# Sheet1.net
KiCad netlist of a schematic drawn in Altium Designer
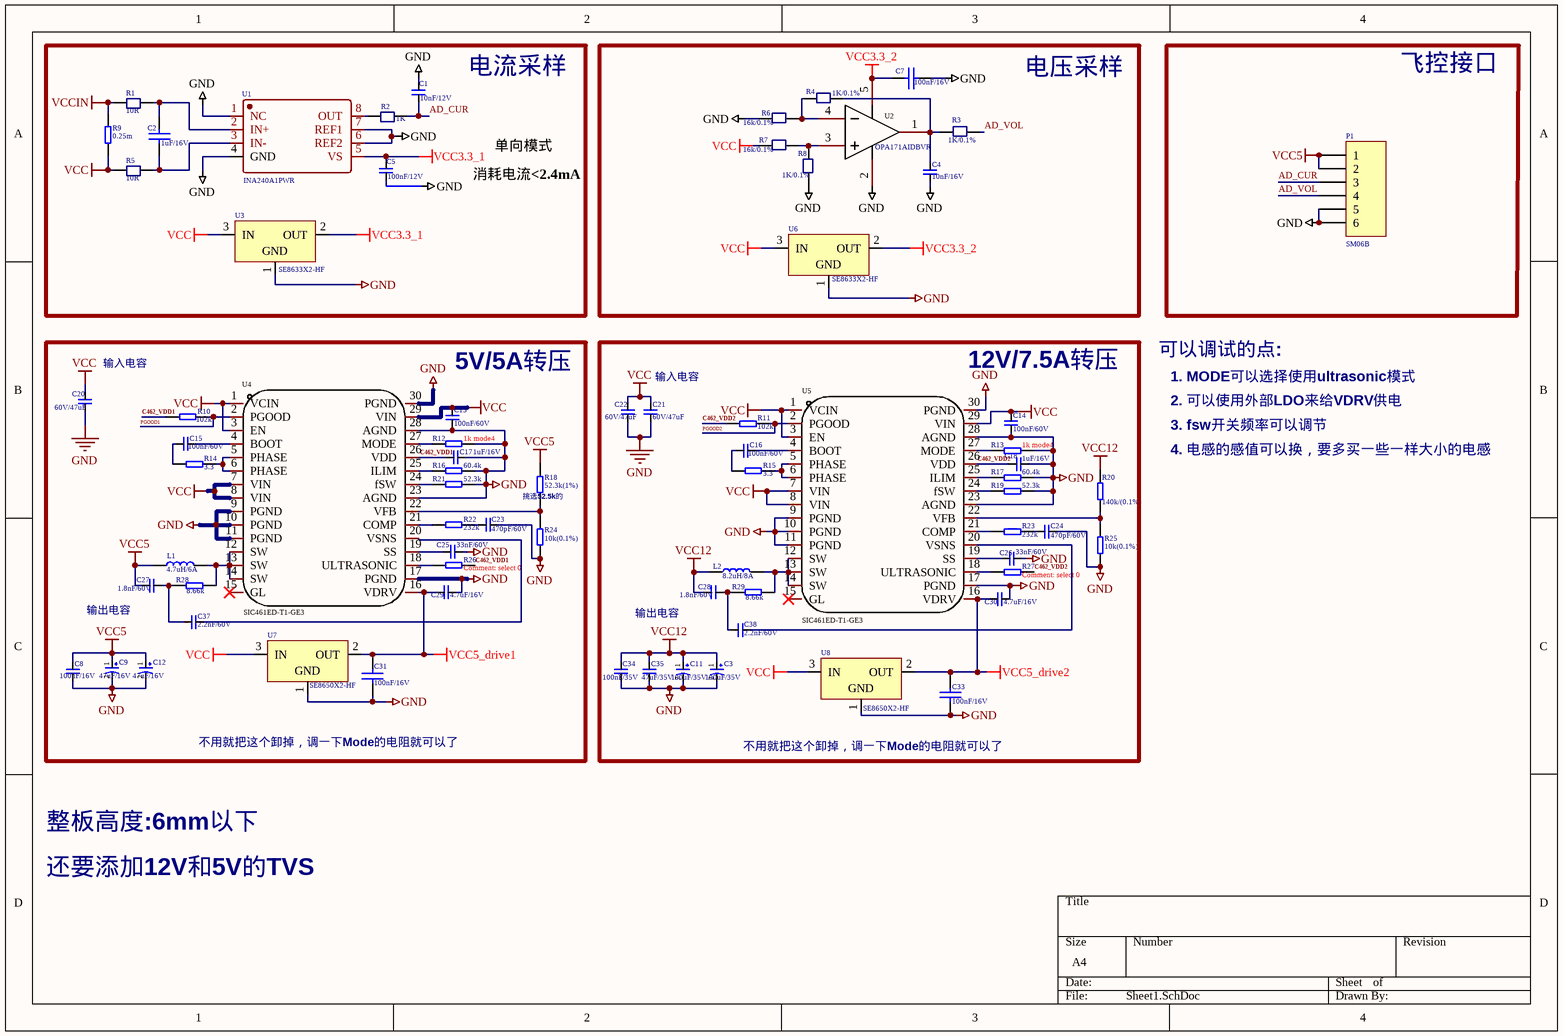
[diagram p0: Sheet1.SchDoc]

(export (version "E")
  (design (tool "Eeschema 10.0.6"))
  (components
    (comp (ref "C1") (value "10nF/12V") (footprint "C0402") (libsource (lib "Schlib1") (part "C")))
    (comp (ref "C2")
      (value "1uF/16V")
      (footprint "C 0603_M")
      (description "Capacitor")
      (fields (field (name "PUBLISHER") "Altium Limited"))
      (libsource (lib "超级电容") (part "Cap"))
    )
    (comp (ref "C3")
      (value "100uF/35V")
      (footprint "CASE-B-3528")
      (description "极性电容\r\n多为大容量铝电解\r\nNPXD0601V101MF\r\n100uF/35V\r\nC2976304")
      (libsource (lib "Schlib1") (part "CP"))
    )
    (comp (ref "C4") (value "10nF/16V") (footprint "C0402") (libsource (lib "Schlib1") (part "C")))
    (comp (ref "C5") (value "100nF/12V") (footprint "C0402") (libsource (lib "Schlib1") (part "C")))
    (comp (ref "C7")
      (value "100nF/16V")
      (footprint "C0402")
      (description "Capacitor")
      (fields (field (name "PUBLISHER") "Altium Limited"))
      (libsource (lib "超级电容") (part "Cap"))
    )
    (comp (ref "C8") (value "100nF/16V") (footprint "C0402") (libsource (lib "Schlib1") (part "C")))
    (comp (ref "C9")
      (value "47uF/16V")
      (footprint "CASE-B-3528")
      (description "极性电容\r\n多为大容量铝电解")
      (libsource (lib "Schlib1") (part "CP"))
    )
    (comp (ref "C11")
      (value "100uF/35V")
      (footprint "CASE-B-3528")
      (description "极性电容\r\n多为大容量铝电解\r\nNPXD0601V101MF\r\n100uF/35V\r\nC2976304")
      (libsource (lib "Schlib1") (part "CP"))
    )
    (comp (ref "C12")
      (value "47uF/16V")
      (footprint "CASE-B-3528")
      (description "极性电容\r\n多为大容量铝电解")
      (libsource (lib "Schlib1") (part "CP"))
    )
    (comp (ref "C13") (value "100nF/60V") (footprint "C0402") (libsource (lib "Schlib1") (part "C")))
    (comp (ref "C14") (value "100nF/60V") (footprint "C0402") (libsource (lib "Schlib1") (part "C")))
    (comp (ref "C15") (value "100nF/60V") (footprint "C0402") (libsource (lib "Schlib1") (part "C")))
    (comp (ref "C16") (value "100nF/60V") (footprint "C0402") (libsource (lib "Schlib1") (part "C")))
    (comp (ref "C17") (value "1uF/16V") (footprint "C0402") (libsource (lib "Schlib1") (part "C")))
    (comp (ref "C18") (value "1uF/16V") (footprint "C0402") (libsource (lib "Schlib1") (part "C")))
    (comp (ref "C20") (value "60V/47uF") (footprint "C 1210") (libsource (lib "Schlib1") (part "C")))
    (comp (ref "C21") (value "60V/47uF") (footprint "C 1210") (libsource (lib "Schlib1") (part "C")))
    (comp (ref "C22") (value "60V/47uF") (footprint "C 1210") (libsource (lib "Schlib1") (part "C")))
    (comp (ref "C23") (value "470pF/60V") (footprint "C0402") (libsource (lib "Schlib1") (part "C")))
    (comp (ref "C24") (value "470pF/60V") (footprint "C 0603_M") (libsource (lib "Schlib1") (part "C")))
    (comp (ref "C25") (value "33nF/60V") (footprint "C0402") (libsource (lib "Schlib1") (part "C")))
    (comp (ref "C26") (value "33nF/60V") (footprint "C0402") (libsource (lib "Schlib1") (part "C")))
    (comp (ref "C27")
      (value "1.8nF/60V")
      (footprint "C0402")
      (description "C1853237")
      (libsource (lib "Schlib1") (part "C"))
    )
    (comp (ref "C28")
      (value "1.8nF/60V")
      (footprint "C0402")
      (description "C1853237")
      (libsource (lib "Schlib1") (part "C"))
    )
    (comp (ref "C29") (value "4.7uF/16V") (footprint "C 0603_M") (libsource (lib "Schlib1") (part "C")))
    (comp (ref "C30") (value "4.7uF/16V") (footprint "C 0603_M") (libsource (lib "Schlib1") (part "C")))
    (comp (ref "C31")
      (value "100nF/16V")
      (footprint "C0402")
      (description "Capacitor")
      (fields (field (name "PUBLISHER") "Altium Limited"))
      (libsource (lib "csy") (part "Cap"))
    )
    (comp (ref "C33")
      (value "100nF/16V")
      (footprint "C0402")
      (description "Capacitor")
      (fields (field (name "PUBLISHER") "Altium Limited"))
      (libsource (lib "csy") (part "Cap"))
    )
    (comp (ref "C34") (value "100nF/35V") (footprint "C0402") (libsource (lib "Schlib1") (part "C")))
    (comp (ref "C35")
      (value "47uF/35V")
      (footprint "CAP-SMD_L3.2-W1.6")
      (libsource (lib "Schlib1") (part "C"))
    )
    (comp (ref "C37")
      (value "2.2nF/60V")
      (footprint "C0402")
      (description "C1853237")
      (libsource (lib "Schlib1") (part "C"))
    )
    (comp (ref "C38")
      (value "2.2nF/60V")
      (footprint "C0402")
      (description "C1853237")
      (libsource (lib "Schlib1") (part "C"))
    )
    (comp (ref "L1")
      (value "4.7uH/6A")
      (footprint "IND-SMD_L7.1-W6.6")
      (description "FXL0650-4R7-M\r\n4.7uH ±20% 6A 6.6mm*7mm*4.8mm\r\nC475520")
      (libsource (lib "Schlib1") (part "L"))
    )
    (comp (ref "L2")
      (value "8.2uH/8A")
      (footprint "IND-SMD_L11.5-W10.0_SMMS1040")
      (description "FXL1040-8R2-M\r\nSMD,11.5*10.0mm*3.8mm\r\nC167202")
      (libsource (lib "Schlib1") (part "L"))
    )
    (comp (ref "P1")
      (value "SM06B")
      (footprint "BM06B-GHS-TBT")
      (description "Header, 6-Pin")
      (fields (field (name "PUBLISHER") "Altium Limited"))
      (libsource (lib "Schlib1") (part "P SM06B"))
    )
    (comp (ref "R1")
      (value "10R")
      (footprint "R0402")
      (description "Resistor")
      (fields (field (name "PUBLISHER") "Altium Limited"))
      (libsource (lib "超级电容") (part "Res"))
    )
    (comp (ref "R2")
      (value "1K")
      (footprint "R0402")
      (description "Resistor")
      (fields (field (name "PUBLISHER") "Altium Limited"))
      (libsource (lib "超级电容") (part "Res"))
    )
    (comp (ref "R3")
      (value "1K/0.1%")
      (footprint "R0402")
      (description "Resistor")
      (fields (field (name "PUBLISHER") "Altium Limited"))
      (libsource (lib "超级电容") (part "Res"))
    )
    (comp (ref "R4")
      (value "1K/0.1%")
      (footprint "R0402")
      (description "Resistor")
      (fields (field (name "PUBLISHER") "Altium Limited"))
      (libsource (lib "超级电容") (part "Res"))
    )
    (comp (ref "R5")
      (value "10R")
      (footprint "R0402")
      (description "Resistor")
      (fields (field (name "PUBLISHER") "Altium Limited"))
      (libsource (lib "超级电容") (part "Res"))
    )
    (comp (ref "R6")
      (value "16k/0.1%")
      (footprint "R0402")
      (description "Resistor")
      (fields (field (name "PUBLISHER") "Altium Limited"))
      (libsource (lib "超级电容") (part "Res"))
    )
    (comp (ref "R7")
      (value "16k/0.1%")
      (footprint "R0402")
      (description "Resistor")
      (fields (field (name "PUBLISHER") "Altium Limited"))
      (libsource (lib "超级电容") (part "Res"))
    )
    (comp (ref "R8")
      (value "1K/0.1%")
      (footprint "R0402")
      (description "Resistor")
      (fields (field (name "PUBLISHER") "Altium Limited"))
      (libsource (lib "超级电容") (part "Res"))
    )
    (comp (ref "R9")
      (value "0.25m")
      (footprint "R1216")
      (description "贴片电阻HoBB1216-5W-0.25-1%\r\nC17701555")
      (fields (field (name "版权归属") "黎明电子style"))
      (libsource (lib "Schlib1") (part "R"))
    )
    (comp (ref "R10")
      (value "102k")
      (footprint "R0402")
      (description "贴片电阻HoBB1216-5W-0.25-1%\r\nC17701555")
      (fields (field (name "版权归属") "黎明电子style"))
      (libsource (lib "Schlib1") (part "R"))
    )
    (comp (ref "R11")
      (value "102k")
      (footprint "R0402")
      (description "贴片电阻HoBB1216-5W-0.25-1%\r\nC17701555")
      (fields (field (name "版权归属") "黎明电子style"))
      (libsource (lib "Schlib1") (part "R"))
    )
    (comp (ref "R12")
      (value "1k mode4")
      (footprint "R0603_M")
      (description "贴片电阻HoBB1216-5W-0.25-1%\r\nC17701555")
      (fields (field (name "版权归属") "黎明电子style"))
      (libsource (lib "Schlib1") (part "R"))
    )
    (comp (ref "R13")
      (value "1k mode4")
      (footprint "R0402")
      (description "贴片电阻HoBB1216-5W-0.25-1%\r\nC17701555")
      (fields (field (name "版权归属") "黎明电子style"))
      (libsource (lib "Schlib1") (part "R"))
    )
    (comp (ref "R14")
      (value "3.3")
      (footprint "R0402")
      (description "贴片电阻HoBB1216-5W-0.25-1%\r\nC17701555")
      (fields (field (name "版权归属") "黎明电子style"))
      (libsource (lib "Schlib1") (part "R"))
    )
    (comp (ref "R15")
      (value "3.3")
      (footprint "R0402")
      (description "贴片电阻HoBB1216-5W-0.25-1%\r\nC17701555")
      (fields (field (name "版权归属") "黎明电子style"))
      (libsource (lib "Schlib1") (part "R"))
    )
    (comp (ref "R16")
      (value "60.4k")
      (footprint "R0402")
      (description "贴片电阻HoBB1216-5W-0.25-1%\r\nC17701555")
      (fields (field (name "版权归属") "黎明电子style"))
      (libsource (lib "Schlib1") (part "R"))
    )
    (comp (ref "R17")
      (value "60.4k")
      (footprint "R0402")
      (description "贴片电阻HoBB1216-5W-0.25-1%\r\nC17701555")
      (fields (field (name "版权归属") "黎明电子style"))
      (libsource (lib "Schlib1") (part "R"))
    )
    (comp (ref "R18")
      (value "52.3k(1%)")
      (footprint "R0402")
      (description "贴片电阻HoBB1216-5W-0.25-1%\r\nC17701555")
      (fields (field (name "版权归属") "黎明电子style"))
      (libsource (lib "Schlib1") (part "R"))
    )
    (comp (ref "R19")
      (value "52.3k")
      (footprint "R0402")
      (description "贴片电阻HoBB1216-5W-0.25-1%\r\nC17701555")
      (fields (field (name "版权归属") "黎明电子style"))
      (libsource (lib "Schlib1") (part "R"))
    )
    (comp (ref "R20")
      (value "140k/(0.1%)")
      (footprint "R0402")
      (description "贴片电阻HoBB1216-5W-0.25-1%\r\nC17701555")
      (fields (field (name "版权归属") "黎明电子style"))
      (libsource (lib "Schlib1") (part "R"))
    )
    (comp (ref "R21")
      (value "52.3k")
      (footprint "R0402")
      (description "贴片电阻HoBB1216-5W-0.25-1%\r\nC17701555")
      (fields (field (name "版权归属") "黎明电子style"))
      (libsource (lib "Schlib1") (part "R"))
    )
    (comp (ref "R22")
      (value "232k")
      (footprint "R0402")
      (description "贴片电阻HoBB1216-5W-0.25-1%\r\nC17701555")
      (fields (field (name "版权归属") "黎明电子style"))
      (libsource (lib "Schlib1") (part "R"))
    )
    (comp (ref "R23")
      (value "232k")
      (footprint "R0603_M")
      (description "贴片电阻HoBB1216-5W-0.25-1%\r\nC17701555")
      (fields (field (name "版权归属") "黎明电子style"))
      (libsource (lib "Schlib1") (part "R"))
    )
    (comp (ref "R24")
      (value "10k(0.1%)")
      (footprint "R0402")
      (description "贴片电阻HoBB1216-5W-0.25-1%\r\nC17701555")
      (fields (field (name "版权归属") "黎明电子style"))
      (libsource (lib "Schlib1") (part "R"))
    )
    (comp (ref "R25")
      (value "10k(0.1%)")
      (footprint "R0402")
      (description "贴片电阻HoBB1216-5W-0.25-1%\r\nC17701555")
      (fields (field (name "版权归属") "黎明电子style"))
      (libsource (lib "Schlib1") (part "R"))
    )
    (comp (ref "R26")
      (value "select 0")
      (footprint "R0402")
      (fields (field (name "版权归属") "黎明电子style"))
      (libsource (lib "Schlib1") (part "R"))
    )
    (comp (ref "R27")
      (value "select 0")
      (footprint "R0402")
      (fields (field (name "版权归属") "黎明电子style"))
      (libsource (lib "Schlib1") (part "R"))
    )
    (comp (ref "R28")
      (value "8.66k")
      (footprint "R0402")
      (description "贴片电阻HoBB1216-5W-0.25-1%\r\nC17701555")
      (fields (field (name "版权归属") "黎明电子style"))
      (libsource (lib "Schlib1") (part "R"))
    )
    (comp (ref "R29")
      (value "8.66k")
      (footprint "R0402")
      (description "贴片电阻HoBB1216-5W-0.25-1%\r\nC17701555")
      (fields (field (name "版权归属") "黎明电子style"))
      (libsource (lib "Schlib1") (part "R"))
    )
    (comp (ref "U1")
      (value "INA240A1PWR")
      (footprint "TSSOP-8_L4.4-W3.0-P0.65-LS6.4-BL")
      (fields (field (name "BOM_SUPPLIER PART") "C93965") (field (name "CONTRIBUTOR") "LCSC"))
      (libsource (lib "altium-import") (part "root_0_INA240A1PWR_"))
    )
    (comp (ref "U2")
      (value "OPA171AIDBVR")
      (footprint "SOT-23-5_L3.0-W1.7-P0.95-LS2.8-BR")
      (fields (field (name "MANUFACTURER") "TI(德州仪器)"))
      (libsource (lib "Schlib1") (part "OPA171AIDBVR"))
    )
    (comp (ref "U3")
      (value "SE8633X2-HF")
      (footprint "SOT_23")
      (description "200mA Low-Dropout Linear Regulator, 3-pin SOT-23")
      (fields
        (field (name "PARTNUMBER") "LM1117T-3.3")
        (field (name "MANUFACTURER") "National Semiconductor")
        (field (name "PUBLISHER") "Altium Limited")
      )
      (libsource (lib "csy") (part "LM1117-3.3"))
    )
    (comp (ref "U4")
      (value "SIC461ED-T1-GE3")
      (footprint "MLP55-27_L5.0-W5.0-P0.50-TL_SIC46XXX")
      (description "5V output")
      (fields (field (name "MANUFACTURER") "VISHAY(威世)"))
      (libsource (lib "Schlib1") (part "U SIC461ED-T1-GE3"))
    )
    (comp (ref "U5")
      (value "SIC461ED-T1-GE3")
      (footprint "MLP55-27_L5.0-W5.0-P0.50-TL_SIC46XXX")
      (description "5V output")
      (fields (field (name "MANUFACTURER") "VISHAY(威世)"))
      (libsource (lib "Schlib1") (part "U SIC461ED-T1-GE3"))
    )
    (comp (ref "U6")
      (value "SE8633X2-HF")
      (footprint "SOT_23")
      (description "200mA Low-Dropout Linear Regulator, 3-pin SOT-23")
      (fields
        (field (name "PARTNUMBER") "LM1117T-3.3")
        (field (name "MANUFACTURER") "National Semiconductor")
        (field (name "PUBLISHER") "Altium Limited")
      )
      (libsource (lib "csy") (part "LM1117-3.3"))
    )
    (comp (ref "U7")
      (value "SE8650X2-HF")
      (footprint "SOT_23")
      (description "200mA Low-Dropout Linear Regulator, 3-pin SOT-23\r\nC496615")
      (fields
        (field (name "PARTNUMBER") "LM1117T-3.3")
        (field (name "MANUFACTURER") "National Semiconductor")
        (field (name "PUBLISHER") "Altium Limited")
      )
      (libsource (lib "csy") (part "LM1117-3.3"))
    )
    (comp (ref "U8")
      (value "SE8650X2-HF")
      (footprint "SOT_23")
      (description "200mA Low-Dropout Linear Regulator, 3-pin SOT-23")
      (fields
        (field (name "PARTNUMBER") "LM1117T-3.3")
        (field (name "MANUFACTURER") "National Semiconductor")
        (field (name "PUBLISHER") "Altium Limited")
      )
      (libsource (lib "csy") (part "LM1117-3.3"))
    )
  )
  (nets
    (net (code "1") (name "/AD_CUR") (class "Default")
      (node (ref "C1") (pin "1") (pinfunction "1_1") (pintype "passive"))
      (node (ref "P1") (pin "3") (pinfunction "3_3") (pintype "passive"))
      (node (ref "R2") (pin "2") (pinfunction "2_2") (pintype "passive"))
    )
    (net (code "2") (name "/AD_VOL") (class "Default")
      (node (ref "P1") (pin "4") (pinfunction "4_4") (pintype "passive"))
      (node (ref "R3") (pin "1") (pinfunction "1_1") (pintype "passive"))
    )
    (net (code "3") (name "/C462_VDD1") (class "Default")
      (node (ref "C17") (pin "2") (pinfunction "2_2") (pintype "passive"))
      (node (ref "R10") (pin "1") (pinfunction "1_1") (pintype "passive"))
      (node (ref "R26") (pin "2") (pinfunction "2_2") (pintype "passive"))
      (node (ref "U4") (pin "26") (pinfunction "VDD_26") (pintype "passive"))
    )
    (net (code "4") (name "/C462_VDD2") (class "Default")
      (node (ref "C18") (pin "2") (pinfunction "2_2") (pintype "passive"))
      (node (ref "R11") (pin "1") (pinfunction "1_1") (pintype "passive"))
      (node (ref "R27") (pin "2") (pinfunction "2_2") (pintype "passive"))
      (node (ref "U5") (pin "26") (pinfunction "VDD_26") (pintype "passive"))
    )
    (net (code "5") (name "/PGOOD1") (class "Default")
      (node (ref "R10") (pin "2") (pinfunction "2_2") (pintype "passive"))
      (node (ref "U4") (pin "2") (pinfunction "PGOOD_2") (pintype "passive"))
    )
    (net (code "6") (name "/PGOOD2") (class "Default")
      (node (ref "R11") (pin "2") (pinfunction "2_2") (pintype "passive"))
      (node (ref "U5") (pin "2") (pinfunction "PGOOD_2") (pintype "passive"))
    )
    (net (code "7") (name "GND") (class "Default")
      (node (ref "C1") (pin "2") (pinfunction "2_2") (pintype "passive"))
      (node (ref "C11") (pin "2") (pinfunction "2_2") (pintype "passive"))
      (node (ref "C12") (pin "2") (pinfunction "2_2") (pintype "passive"))
      (node (ref "C13") (pin "1") (pinfunction "1_1") (pintype "passive"))
      (node (ref "C14") (pin "1") (pinfunction "1_1") (pintype "passive"))
      (node (ref "C17") (pin "1") (pinfunction "1_1") (pintype "passive"))
      (node (ref "C18") (pin "1") (pinfunction "1_1") (pintype "passive"))
      (node (ref "C20") (pin "2") (pinfunction "2_2") (pintype "passive"))
      (node (ref "C21") (pin "2") (pinfunction "2_2") (pintype "passive"))
      (node (ref "C22") (pin "2") (pinfunction "2_2") (pintype "passive"))
      (node (ref "C23") (pin "1") (pinfunction "1_1") (pintype "passive"))
      (node (ref "C24") (pin "1") (pinfunction "1_1") (pintype "passive"))
      (node (ref "C25") (pin "1") (pinfunction "1_1") (pintype "passive"))
      (node (ref "C26") (pin "1") (pinfunction "1_1") (pintype "passive"))
      (node (ref "C29") (pin "1") (pinfunction "1_1") (pintype "passive"))
      (node (ref "C3") (pin "2") (pinfunction "2_2") (pintype "passive"))
      (node (ref "C30") (pin "1") (pinfunction "1_1") (pintype "passive"))
      (node (ref "C31") (pin "1") (pinfunction "1_1") (pintype "passive"))
      (node (ref "C33") (pin "1") (pinfunction "1_1") (pintype "passive"))
      (node (ref "C34") (pin "2") (pinfunction "2_2") (pintype "passive"))
      (node (ref "C35") (pin "2") (pinfunction "2_2") (pintype "passive"))
      (node (ref "C4") (pin "2") (pinfunction "2_2") (pintype "passive"))
      (node (ref "C5") (pin "1") (pinfunction "1_1") (pintype "passive"))
      (node (ref "C7") (pin "2") (pinfunction "2_2") (pintype "passive"))
      (node (ref "C8") (pin "2") (pinfunction "2_2") (pintype "passive"))
      (node (ref "C9") (pin "2") (pinfunction "2_2") (pintype "passive"))
      (node (ref "P1") (pin "5") (pinfunction "5_5") (pintype "passive"))
      (node (ref "P1") (pin "6") (pinfunction "6_6") (pintype "passive"))
      (node (ref "R12") (pin "2") (pinfunction "2_2") (pintype "passive"))
      (node (ref "R13") (pin "2") (pinfunction "2_2") (pintype "passive"))
      (node (ref "R16") (pin "2") (pinfunction "2_2") (pintype "passive"))
      (node (ref "R17") (pin "2") (pinfunction "2_2") (pintype "passive"))
      (node (ref "R19") (pin "2") (pinfunction "2_2") (pintype "passive"))
      (node (ref "R21") (pin "2") (pinfunction "2_2") (pintype "passive"))
      (node (ref "R24") (pin "2") (pinfunction "2_2") (pintype "passive"))
      (node (ref "R25") (pin "2") (pinfunction "2_2") (pintype "passive"))
      (node (ref "R6") (pin "2") (pinfunction "2_2") (pintype "passive"))
      (node (ref "R8") (pin "2") (pinfunction "2_2") (pintype "passive"))
      (node (ref "U1") (pin "1") (pinfunction "NC_1") (pintype "passive"))
      (node (ref "U1") (pin "4") (pinfunction "GND_4") (pintype "passive"))
      (node (ref "U1") (pin "6") (pinfunction "REF2_6") (pintype "passive"))
      (node (ref "U1") (pin "7") (pinfunction "REF1_7") (pintype "passive"))
      (node (ref "U2") (pin "2") (pinfunction "V-_2") (pintype "passive"))
      (node (ref "U3") (pin "1") (pinfunction "GND_1") (pintype "power_in"))
      (node (ref "U4") (pin "10") (pinfunction "PGND_10") (pintype "passive"))
      (node (ref "U4") (pin "11") (pinfunction "PGND_11") (pintype "passive"))
      (node (ref "U4") (pin "17") (pinfunction "PGND_17") (pintype "passive"))
      (node (ref "U4") (pin "23") (pinfunction "AGND_23") (pintype "passive"))
      (node (ref "U4") (pin "28") (pinfunction "AGND_28") (pintype "passive"))
      (node (ref "U4") (pin "30") (pinfunction "PGND_30") (pintype "passive"))
      (node (ref "U4") (pin "9") (pinfunction "PGND_9") (pintype "passive"))
      (node (ref "U5") (pin "10") (pinfunction "PGND_10") (pintype "passive"))
      (node (ref "U5") (pin "11") (pinfunction "PGND_11") (pintype "passive"))
      (node (ref "U5") (pin "17") (pinfunction "PGND_17") (pintype "passive"))
      (node (ref "U5") (pin "23") (pinfunction "AGND_23") (pintype "passive"))
      (node (ref "U5") (pin "28") (pinfunction "AGND_28") (pintype "passive"))
      (node (ref "U5") (pin "30") (pinfunction "PGND_30") (pintype "passive"))
      (node (ref "U5") (pin "9") (pinfunction "PGND_9") (pintype "passive"))
      (node (ref "U6") (pin "1") (pinfunction "GND_1") (pintype "power_in"))
      (node (ref "U7") (pin "1") (pinfunction "GND_1") (pintype "power_in"))
      (node (ref "U8") (pin "1") (pinfunction "GND_1") (pintype "power_in"))
    )
    (net (code "8") (name "Net-(C15-Pad2)") (class "Default")
      (node (ref "C15") (pin "2") (pinfunction "2_2") (pintype "passive"))
      (node (ref "R14") (pin "1") (pinfunction "1_1") (pintype "passive"))
    )
    (net (code "9") (name "Net-(C16-Pad2)") (class "Default")
      (node (ref "C16") (pin "2") (pinfunction "2_2") (pintype "passive"))
      (node (ref "R15") (pin "1") (pinfunction "1_1") (pintype "passive"))
    )
    (net (code "10") (name "Net-(C23-Pad2)") (class "Default")
      (node (ref "C23") (pin "2") (pinfunction "2_2") (pintype "passive"))
      (node (ref "R22") (pin "2") (pinfunction "2_2") (pintype "passive"))
    )
    (net (code "11") (name "Net-(C24-Pad2)") (class "Default")
      (node (ref "C24") (pin "2") (pinfunction "2_2") (pintype "passive"))
      (node (ref "R23") (pin "2") (pinfunction "2_2") (pintype "passive"))
    )
    (net (code "12") (name "Net-(C27-Pad1)") (class "Default")
      (node (ref "C27") (pin "1") (pinfunction "1_1") (pintype "passive"))
      (node (ref "C37") (pin "2") (pinfunction "2_2") (pintype "passive"))
      (node (ref "R28") (pin "1") (pinfunction "1_1") (pintype "passive"))
    )
    (net (code "13") (name "Net-(C28-Pad1)") (class "Default")
      (node (ref "C28") (pin "1") (pinfunction "1_1") (pintype "passive"))
      (node (ref "C38") (pin "2") (pinfunction "2_2") (pintype "passive"))
      (node (ref "R29") (pin "1") (pinfunction "1_1") (pintype "passive"))
    )
    (net (code "14") (name "Net-(L1-Pad2)") (class "Default")
      (node (ref "L1") (pin "2") (pinfunction "2_2") (pintype "passive"))
      (node (ref "R28") (pin "2") (pinfunction "2_2") (pintype "passive"))
      (node (ref "U4") (pin "12") (pinfunction "SW_12") (pintype "passive"))
      (node (ref "U4") (pin "13") (pinfunction "SW_13") (pintype "passive"))
      (node (ref "U4") (pin "14") (pinfunction "SW_14") (pintype "passive"))
    )
    (net (code "15") (name "Net-(L2-Pad2)") (class "Default")
      (node (ref "L2") (pin "2") (pinfunction "2_2") (pintype "passive"))
      (node (ref "R29") (pin "2") (pinfunction "2_2") (pintype "passive"))
      (node (ref "U5") (pin "12") (pinfunction "SW_12") (pintype "passive"))
      (node (ref "U5") (pin "13") (pinfunction "SW_13") (pintype "passive"))
      (node (ref "U5") (pin "14") (pinfunction "SW_14") (pintype "passive"))
    )
    (net (code "16") (name "Net-(R14-Pad2)") (class "Default")
      (node (ref "R14") (pin "2") (pinfunction "2_2") (pintype "passive"))
      (node (ref "U4") (pin "5") (pinfunction "PHASE_5") (pintype "passive"))
      (node (ref "U4") (pin "6") (pinfunction "PHASE_6") (pintype "passive"))
    )
    (net (code "17") (name "Net-(R15-Pad2)") (class "Default")
      (node (ref "R15") (pin "2") (pinfunction "2_2") (pintype "passive"))
      (node (ref "U5") (pin "5") (pinfunction "PHASE_5") (pintype "passive"))
      (node (ref "U5") (pin "6") (pinfunction "PHASE_6") (pintype "passive"))
    )
    (net (code "18") (name "Net-(U1-IN+)") (class "Default")
      (node (ref "C2") (pin "2") (pinfunction "2_2") (pintype "passive"))
      (node (ref "R1") (pin "2") (pinfunction "2_2") (pintype "passive"))
      (node (ref "U1") (pin "2") (pinfunction "IN+_2") (pintype "passive"))
    )
    (net (code "19") (name "Net-(U1-IN-)") (class "Default")
      (node (ref "C2") (pin "1") (pinfunction "1_1") (pintype "passive"))
      (node (ref "R5") (pin "2") (pinfunction "2_2") (pintype "passive"))
      (node (ref "U1") (pin "3") (pinfunction "IN-_3") (pintype "passive"))
    )
    (net (code "20") (name "Net-(U1-OUT)") (class "Default")
      (node (ref "R2") (pin "1") (pinfunction "1_1") (pintype "passive"))
      (node (ref "U1") (pin "8") (pinfunction "OUT_8") (pintype "passive"))
    )
    (net (code "21") (name "Net-(U2-IN+)") (class "Default")
      (node (ref "R7") (pin "1") (pinfunction "1_1") (pintype "passive"))
      (node (ref "R8") (pin "1") (pinfunction "1_1") (pintype "passive"))
      (node (ref "U2") (pin "3") (pinfunction "IN+_3") (pintype "passive"))
    )
    (net (code "22") (name "Net-(U2-IN-)") (class "Default")
      (node (ref "R4") (pin "2") (pinfunction "2_2") (pintype "passive"))
      (node (ref "R6") (pin "1") (pinfunction "1_1") (pintype "passive"))
      (node (ref "U2") (pin "4") (pinfunction "IN-_4") (pintype "passive"))
    )
    (net (code "23") (name "Net-(U2-OUT)") (class "Default")
      (node (ref "C4") (pin "1") (pinfunction "1_1") (pintype "passive"))
      (node (ref "R3") (pin "2") (pinfunction "2_2") (pintype "passive"))
      (node (ref "R4") (pin "1") (pinfunction "1_1") (pintype "passive"))
      (node (ref "U2") (pin "1") (pinfunction "OUT_1") (pintype "passive"))
    )
    (net (code "24") (name "Net-(U4-BOOT)") (class "Default")
      (node (ref "C15") (pin "1") (pinfunction "1_1") (pintype "passive"))
      (node (ref "U4") (pin "4") (pinfunction "BOOT_4") (pintype "passive"))
    )
    (net (code "25") (name "Net-(U4-COMP)") (class "Default")
      (node (ref "R22") (pin "1") (pinfunction "1_1") (pintype "passive"))
      (node (ref "U4") (pin "21") (pinfunction "COMP_21") (pintype "passive"))
    )
    (net (code "26") (name "Net-(U4-ILIM)") (class "Default")
      (node (ref "R16") (pin "1") (pinfunction "1_1") (pintype "passive"))
      (node (ref "U4") (pin "25") (pinfunction "ILIM_25") (pintype "passive"))
    )
    (net (code "27") (name "Net-(U4-MODE)") (class "Default")
      (node (ref "R12") (pin "1") (pinfunction "1_1") (pintype "passive"))
      (node (ref "U4") (pin "27") (pinfunction "MODE_27") (pintype "passive"))
    )
    (net (code "28") (name "Net-(U4-SS)") (class "Default")
      (node (ref "C25") (pin "2") (pinfunction "2_2") (pintype "passive"))
      (node (ref "U4") (pin "19") (pinfunction "SS_19") (pintype "passive"))
    )
    (net (code "29") (name "Net-(U4-ULTRASONIC)") (class "Default")
      (node (ref "R26") (pin "1") (pinfunction "1_1") (pintype "passive"))
      (node (ref "U4") (pin "18") (pinfunction "ULTRASONIC_18") (pintype "passive"))
    )
    (net (code "30") (name "Net-(U4-VFB)") (class "Default")
      (node (ref "R18") (pin "1") (pinfunction "1_1") (pintype "passive"))
      (node (ref "R24") (pin "1") (pinfunction "1_1") (pintype "passive"))
      (node (ref "U4") (pin "22") (pinfunction "VFB_22") (pintype "passive"))
    )
    (net (code "31") (name "Net-(U4-VSNS)") (class "Default")
      (node (ref "C37") (pin "1") (pinfunction "1_1") (pintype "passive"))
      (node (ref "U4") (pin "20") (pinfunction "VSNS_20") (pintype "passive"))
    )
    (net (code "32") (name "Net-(U4-fSW)") (class "Default")
      (node (ref "R21") (pin "1") (pinfunction "1_1") (pintype "passive"))
      (node (ref "U4") (pin "24") (pinfunction "fSW_24") (pintype "passive"))
    )
    (net (code "33") (name "Net-(U5-BOOT)") (class "Default")
      (node (ref "C16") (pin "1") (pinfunction "1_1") (pintype "passive"))
      (node (ref "U5") (pin "4") (pinfunction "BOOT_4") (pintype "passive"))
    )
    (net (code "34") (name "Net-(U5-COMP)") (class "Default")
      (node (ref "R23") (pin "1") (pinfunction "1_1") (pintype "passive"))
      (node (ref "U5") (pin "21") (pinfunction "COMP_21") (pintype "passive"))
    )
    (net (code "35") (name "Net-(U5-ILIM)") (class "Default")
      (node (ref "R17") (pin "1") (pinfunction "1_1") (pintype "passive"))
      (node (ref "U5") (pin "25") (pinfunction "ILIM_25") (pintype "passive"))
    )
    (net (code "36") (name "Net-(U5-MODE)") (class "Default")
      (node (ref "R13") (pin "1") (pinfunction "1_1") (pintype "passive"))
      (node (ref "U5") (pin "27") (pinfunction "MODE_27") (pintype "passive"))
    )
    (net (code "37") (name "Net-(U5-SS)") (class "Default")
      (node (ref "C26") (pin "2") (pinfunction "2_2") (pintype "passive"))
      (node (ref "U5") (pin "19") (pinfunction "SS_19") (pintype "passive"))
    )
    (net (code "38") (name "Net-(U5-ULTRASONIC)") (class "Default")
      (node (ref "R27") (pin "1") (pinfunction "1_1") (pintype "passive"))
      (node (ref "U5") (pin "18") (pinfunction "ULTRASONIC_18") (pintype "passive"))
    )
    (net (code "39") (name "Net-(U5-VFB)") (class "Default")
      (node (ref "R20") (pin "1") (pinfunction "1_1") (pintype "passive"))
      (node (ref "R25") (pin "1") (pinfunction "1_1") (pintype "passive"))
      (node (ref "U5") (pin "22") (pinfunction "VFB_22") (pintype "passive"))
    )
    (net (code "40") (name "Net-(U5-VSNS)") (class "Default")
      (node (ref "C38") (pin "1") (pinfunction "1_1") (pintype "passive"))
      (node (ref "U5") (pin "20") (pinfunction "VSNS_20") (pintype "passive"))
    )
    (net (code "41") (name "Net-(U5-fSW)") (class "Default")
      (node (ref "R19") (pin "1") (pinfunction "1_1") (pintype "passive"))
      (node (ref "U5") (pin "24") (pinfunction "fSW_24") (pintype "passive"))
    )
    (net (code "42") (name "VCC") (class "Default")
      (node (ref "C13") (pin "2") (pinfunction "2_2") (pintype "passive"))
      (node (ref "C14") (pin "2") (pinfunction "2_2") (pintype "passive"))
      (node (ref "C20") (pin "1") (pinfunction "1_1") (pintype "passive"))
      (node (ref "C21") (pin "1") (pinfunction "1_1") (pintype "passive"))
      (node (ref "C22") (pin "1") (pinfunction "1_1") (pintype "passive"))
      (node (ref "R5") (pin "1") (pinfunction "1_1") (pintype "passive"))
      (node (ref "R7") (pin "2") (pinfunction "2_2") (pintype "passive"))
      (node (ref "R9") (pin "2") (pinfunction "2_2") (pintype "passive"))
      (node (ref "U3") (pin "3") (pinfunction "IN_3") (pintype "power_in"))
      (node (ref "U4") (pin "1") (pinfunction "VCIN_1") (pintype "passive"))
      (node (ref "U4") (pin "29") (pinfunction "VIN_29") (pintype "passive"))
      (node (ref "U4") (pin "3") (pinfunction "EN_3") (pintype "passive"))
      (node (ref "U4") (pin "7") (pinfunction "VIN_7") (pintype "passive"))
      (node (ref "U4") (pin "8") (pinfunction "VIN_8") (pintype "passive"))
      (node (ref "U5") (pin "1") (pinfunction "VCIN_1") (pintype "passive"))
      (node (ref "U5") (pin "29") (pinfunction "VIN_29") (pintype "passive"))
      (node (ref "U5") (pin "3") (pinfunction "EN_3") (pintype "passive"))
      (node (ref "U5") (pin "7") (pinfunction "VIN_7") (pintype "passive"))
      (node (ref "U5") (pin "8") (pinfunction "VIN_8") (pintype "passive"))
      (node (ref "U6") (pin "3") (pinfunction "IN_3") (pintype "power_in"))
      (node (ref "U7") (pin "3") (pinfunction "IN_3") (pintype "power_in"))
      (node (ref "U8") (pin "3") (pinfunction "IN_3") (pintype "power_in"))
    )
    (net (code "43") (name "VCC3.3_1") (class "Default")
      (node (ref "C5") (pin "2") (pinfunction "2_2") (pintype "passive"))
      (node (ref "U1") (pin "5") (pinfunction "VS_5") (pintype "passive"))
      (node (ref "U3") (pin "2") (pinfunction "OUT_2") (pintype "power_in"))
    )
    (net (code "44") (name "VCC3.3_2") (class "Default")
      (node (ref "C7") (pin "1") (pinfunction "1_1") (pintype "passive"))
      (node (ref "U2") (pin "5") (pinfunction "V+_5") (pintype "passive"))
      (node (ref "U6") (pin "2") (pinfunction "OUT_2") (pintype "power_in"))
    )
    (net (code "45") (name "VCC5") (class "Default")
      (node (ref "C12") (pin "1") (pinfunction "1_1") (pintype "passive"))
      (node (ref "C27") (pin "2") (pinfunction "2_2") (pintype "passive"))
      (node (ref "C8") (pin "1") (pinfunction "1_1") (pintype "passive"))
      (node (ref "C9") (pin "1") (pinfunction "1_1") (pintype "passive"))
      (node (ref "L1") (pin "1") (pinfunction "1_1") (pintype "passive"))
      (node (ref "P1") (pin "1") (pinfunction "1_1") (pintype "passive"))
      (node (ref "P1") (pin "2") (pinfunction "2_2") (pintype "passive"))
      (node (ref "R18") (pin "2") (pinfunction "2_2") (pintype "passive"))
    )
    (net (code "46") (name "VCC5_drive1") (class "Default")
      (node (ref "C29") (pin "2") (pinfunction "2_2") (pintype "passive"))
      (node (ref "C31") (pin "2") (pinfunction "2_2") (pintype "passive"))
      (node (ref "U4") (pin "16") (pinfunction "VDRV_16") (pintype "passive"))
      (node (ref "U7") (pin "2") (pinfunction "OUT_2") (pintype "power_in"))
    )
    (net (code "47") (name "VCC5_drive2") (class "Default")
      (node (ref "C30") (pin "2") (pinfunction "2_2") (pintype "passive"))
      (node (ref "C33") (pin "2") (pinfunction "2_2") (pintype "passive"))
      (node (ref "U5") (pin "16") (pinfunction "VDRV_16") (pintype "passive"))
      (node (ref "U8") (pin "2") (pinfunction "OUT_2") (pintype "power_in"))
    )
    (net (code "48") (name "VCC12") (class "Default")
      (node (ref "C11") (pin "1") (pinfunction "1_1") (pintype "passive"))
      (node (ref "C28") (pin "2") (pinfunction "2_2") (pintype "passive"))
      (node (ref "C3") (pin "1") (pinfunction "1_1") (pintype "passive"))
      (node (ref "C34") (pin "1") (pinfunction "1_1") (pintype "passive"))
      (node (ref "C35") (pin "1") (pinfunction "1_1") (pintype "passive"))
      (node (ref "L2") (pin "1") (pinfunction "1_1") (pintype "passive"))
      (node (ref "R20") (pin "2") (pinfunction "2_2") (pintype "passive"))
    )
    (net (code "49") (name "VCCIN") (class "Default")
      (node (ref "R1") (pin "1") (pinfunction "1_1") (pintype "passive"))
      (node (ref "R9") (pin "1") (pinfunction "1_1") (pintype "passive"))
    )
    (net (code "50") (name "unconnected-(U4-GL-Pad15)") (class "Default")
      (node (ref "U4") (pin "15") (pinfunction "GL_15") (pintype "passive+no_connect"))
    )
    (net (code "51") (name "unconnected-(U5-GL-Pad15)") (class "Default")
      (node (ref "U5") (pin "15") (pinfunction "GL_15") (pintype "passive+no_connect"))
    )
  )
)
